# Gemma_M0_rev_D_PyCon.net
KiCad netlist of a schematic drawn in EAGLE
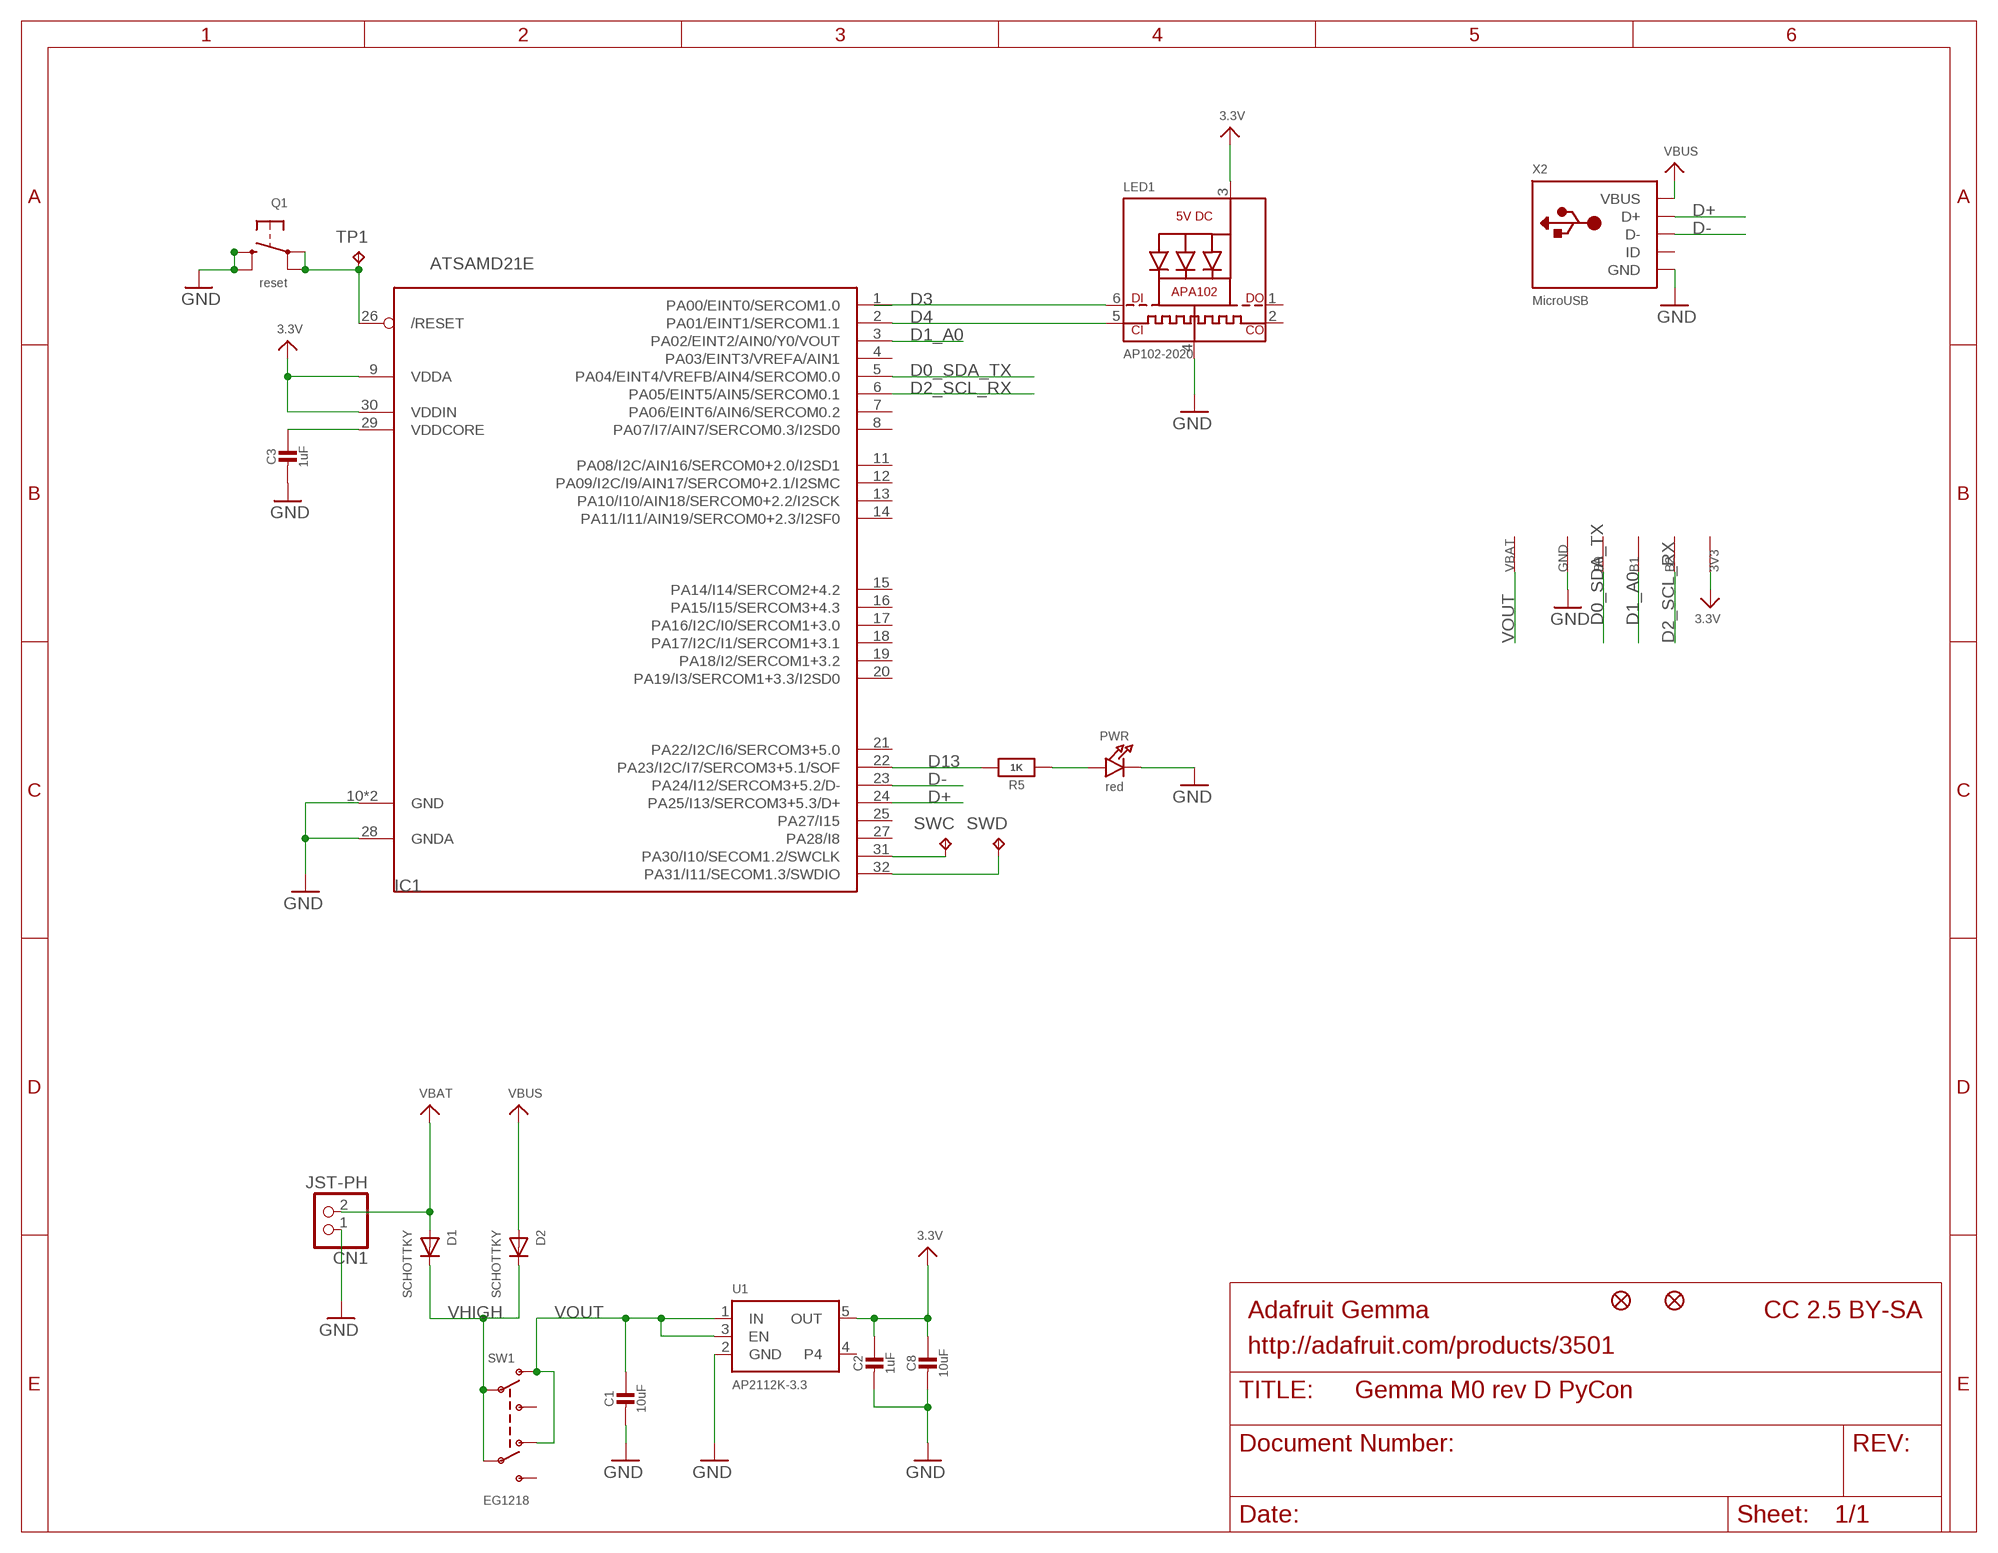
[diagram p0: schematic, sheet 1]

(export (version "E")
  (design (tool "Eeschema 10.0.6"))
  (components
    (comp (ref "3V3")
      (value "SEWTAP-ALLIGATOR")
      (footprint "eagle-import:SEWALLI")
      (libsource (lib "eagle-import") (part "SEWTAP-ALLIGATOR"))
    )
    (comp (ref "B0")
      (value "SEWTAP-ALLIGATOR")
      (footprint "eagle-import:SEWALLI")
      (libsource (lib "eagle-import") (part "SEWTAP-ALLIGATOR"))
    )
    (comp (ref "B1")
      (value "SEWTAP-ALLIGATOR")
      (footprint "eagle-import:SEWALLI")
      (libsource (lib "eagle-import") (part "SEWTAP-ALLIGATOR"))
    )
    (comp (ref "B2")
      (value "SEWTAP-ALLIGATOR")
      (footprint "eagle-import:SEWALLI")
      (libsource (lib "eagle-import") (part "SEWTAP-ALLIGATOR"))
    )
    (comp (ref "C1")
      (value "10uF")
      (footprint "eagle-import:0805-NO")
      (libsource (lib "eagle-import") (part "CAP_CERAMIC0805-NOOUTLINE"))
    )
    (comp (ref "C2")
      (value "1uF")
      (footprint "eagle-import:0603-NO")
      (libsource (lib "eagle-import") (part "CAP_CERAMIC0603_NO"))
    )
    (comp (ref "C3")
      (value "1uF")
      (footprint "eagle-import:0603-NO")
      (libsource (lib "eagle-import") (part "CAP_CERAMIC0603_NO"))
    )
    (comp (ref "C8")
      (value "10uF")
      (footprint "eagle-import:0805-NO")
      (libsource (lib "eagle-import") (part "CAP_CERAMIC0805-NOOUTLINE"))
    )
    (comp (ref "CN1")
      (value "JST-PH")
      (footprint "eagle-import:JSTPH2")
      (libsource (lib "eagle-import") (part "CON_JST_PH_2PIN"))
    )
    (comp (ref "D1")
      (value "SCHOTTKY")
      (footprint "eagle-import:SOD-123FL")
      (libsource (lib "eagle-import") (part "DIODE_SOD-123FL"))
    )
    (comp (ref "D2")
      (value "SCHOTTKY")
      (footprint "eagle-import:SOD-123FL")
      (libsource (lib "eagle-import") (part "DIODE_SOD-123FL"))
    )
    (comp (ref "GND")
      (value "SEWTAP-ALLIGATOR")
      (footprint "eagle-import:SEWALLI")
      (libsource (lib "eagle-import") (part "SEWTAP-ALLIGATOR"))
    )
    (comp (ref "IC1")
      (value "ATSAMD21E")
      (footprint "eagle-import:QFN32_5MM")
      (libsource (lib "eagle-import") (part "ATSAMD21E"))
    )
    (comp (ref "LED1")
      (value "AP102-2020")
      (footprint "eagle-import:APA102_2020")
      (libsource (lib "eagle-import") (part "APA1022020"))
    )
    (comp (ref "PWR")
      (value "red")
      (footprint "eagle-import:CHIPLED_0603_NOOUTLINE")
      (libsource (lib "eagle-import") (part "LED0603_NOOUTLINE"))
    )
    (comp (ref "Q1")
      (value "reset")
      (footprint "eagle-import:BTN_KMR2_4.6X2.8")
      (libsource (lib "eagle-import") (part "SWITCH_TACT_SMT4.6X2.8"))
    )
    (comp (ref "R5")
      (value "1K")
      (footprint "eagle-import:0603-NO")
      (libsource (lib "eagle-import") (part "RESISTOR_0603_NOOUT"))
    )
    (comp (ref "SW1")
      (value "EG1218")
      (footprint "eagle-import:EG1390")
      (libsource (lib "eagle-import") (part "SWITCH_DPDTEG1390"))
    )
    (comp (ref "SWC")
      (value "TPTP15R")
      (footprint "eagle-import:TP15R")
      (libsource (lib "eagle-import") (part "TPTP15R"))
    )
    (comp (ref "SWD")
      (value "TPTP15R")
      (footprint "eagle-import:TP15R")
      (libsource (lib "eagle-import") (part "TPTP15R"))
    )
    (comp (ref "TP1")
      (value "TPTP16R")
      (footprint "eagle-import:TP16R")
      (libsource (lib "eagle-import") (part "TPTP16R"))
    )
    (comp (ref "U$1")
      (value "FIDUCIAL_1MM")
      (footprint "eagle-import:FIDUCIAL_1MM")
      (libsource (lib "eagle-import") (part "FIDUCIAL_1MM"))
    )
    (comp (ref "U$6")
      (value "FIDUCIAL_1MM")
      (footprint "eagle-import:FIDUCIAL_1MM")
      (libsource (lib "eagle-import") (part "FIDUCIAL_1MM"))
    )
    (comp (ref "U1")
      (value "AP2112K-3.3")
      (footprint "eagle-import:SOT23-5")
      (libsource (lib "eagle-import") (part "VREG_SOT23-5"))
    )
    (comp (ref "VBAT")
      (value "SEWTAP-ALLIGATOR")
      (footprint "eagle-import:SEWALLI")
      (libsource (lib "eagle-import") (part "SEWTAP-ALLIGATOR"))
    )
    (comp (ref "X2")
      (value "MicroUSB")
      (footprint "eagle-import:4UCONN_20329_V2")
      (libsource (lib "eagle-import") (part "USB_MICRO_20329_V2"))
    )
  )
  (nets
    (net (code "1") (name "/D+") (class "Default")
      (node (ref "IC1") (pin "24") (pinfunction "PA25/I13/SERCOM3+5.3/D+_24") (pintype "bidirectional"))
      (node (ref "X2") (pin "D+") (pinfunction "D+_D+") (pintype "bidirectional"))
    )
    (net (code "2") (name "/D-") (class "Default")
      (node (ref "IC1") (pin "23") (pinfunction "PA24/I12/SERCOM3+5.2/D-_23") (pintype "bidirectional"))
      (node (ref "X2") (pin "D-") (pinfunction "D-_D-") (pintype "bidirectional"))
    )
    (net (code "3") (name "/D0_SDA_TX") (class "Default")
      (node (ref "B0") (pin "P$1") (pinfunction "SEW_P$1") (pintype "bidirectional"))
      (node (ref "IC1") (pin "5") (pinfunction "PA04/EINT4/VREFB/AIN4/SERCOM0.0_5") (pintype "bidirectional"))
    )
    (net (code "4") (name "/D1_A0") (class "Default")
      (node (ref "B1") (pin "P$1") (pinfunction "SEW_P$1") (pintype "bidirectional"))
      (node (ref "IC1") (pin "3") (pinfunction "PA02/EINT2/AIN0/Y0/VOUT_3") (pintype "bidirectional"))
    )
    (net (code "5") (name "/D2_SCL_RX") (class "Default")
      (node (ref "B2") (pin "P$1") (pinfunction "SEW_P$1") (pintype "bidirectional"))
      (node (ref "IC1") (pin "6") (pinfunction "PA05/EINT5/AIN5/SERCOM0.1_6") (pintype "bidirectional"))
    )
    (net (code "6") (name "/D3") (class "Default")
      (node (ref "IC1") (pin "1") (pinfunction "PA00/EINT0/SERCOM1.0_1") (pintype "bidirectional"))
      (node (ref "LED1") (pin "6") (pinfunction "DI_6") (pintype "input"))
    )
    (net (code "7") (name "/D4") (class "Default")
      (node (ref "IC1") (pin "2") (pinfunction "PA01/EINT1/SERCOM1.1_2") (pintype "bidirectional"))
      (node (ref "LED1") (pin "5") (pinfunction "CKI_5") (pintype "input"))
    )
    (net (code "8") (name "/D13") (class "Default")
      (node (ref "IC1") (pin "22") (pinfunction "PA23/I2C/I7/SERCOM3+5.1/SOF_22") (pintype "bidirectional"))
      (node (ref "R5") (pin "2") (pinfunction "2_2") (pintype "passive"))
    )
    (net (code "9") (name "/VHIGH") (class "Default")
      (node (ref "D1") (pin "C") (pinfunction "C_C") (pintype "passive"))
      (node (ref "D2") (pin "C") (pinfunction "C_C") (pintype "passive"))
      (node (ref "SW1") (pin "P1") (pinfunction "P1_P1") (pintype "passive"))
      (node (ref "SW1") (pin "P2") (pinfunction "P2_P2") (pintype "passive"))
    )
    (net (code "10") (name "/VOUT") (class "Default")
      (node (ref "C1") (pin "1") (pinfunction "1_1") (pintype "passive"))
      (node (ref "SW1") (pin "O1") (pinfunction "O1_O1") (pintype "passive"))
      (node (ref "SW1") (pin "O2") (pinfunction "O2_O2") (pintype "passive"))
      (node (ref "U1") (pin "1") (pinfunction "IN_1") (pintype "power_in"))
      (node (ref "U1") (pin "3") (pinfunction "EN_3") (pintype "input"))
      (node (ref "VBAT") (pin "P$1") (pinfunction "SEW_P$1") (pintype "bidirectional"))
    )
    (net (code "11") (name "3.3V") (class "Default")
      (node (ref "3V3") (pin "P$1") (pinfunction "SEW_P$1") (pintype "bidirectional"))
      (node (ref "C2") (pin "1") (pinfunction "1_1") (pintype "passive"))
      (node (ref "C8") (pin "1") (pinfunction "1_1") (pintype "passive"))
      (node (ref "IC1") (pin "30") (pinfunction "VDDIN_30") (pintype "power_in"))
      (node (ref "IC1") (pin "9") (pinfunction "VDDA_9") (pintype "power_in"))
      (node (ref "LED1") (pin "3") (pinfunction "VDD_3") (pintype "power_in"))
      (node (ref "U1") (pin "5") (pinfunction "OUT_5") (pintype "power_in"))
    )
    (net (code "12") (name "GND") (class "Default")
      (node (ref "C1") (pin "2") (pinfunction "2_2") (pintype "passive"))
      (node (ref "C2") (pin "2") (pinfunction "2_2") (pintype "passive"))
      (node (ref "C3") (pin "2") (pinfunction "2_2") (pintype "passive"))
      (node (ref "C8") (pin "2") (pinfunction "2_2") (pintype "passive"))
      (node (ref "CN1") (pin "1") (pinfunction "1_1") (pintype "passive"))
      (node (ref "GND") (pin "P$1") (pinfunction "SEW_P$1") (pintype "bidirectional"))
      (node (ref "IC1") (pin "10") (pinfunction "GND_10") (pintype "power_in"))
      (node (ref "IC1") (pin "28") (pinfunction "GNDA_28") (pintype "power_in"))
      (node (ref "IC1") (pin "33") (pinfunction "GND_33") (pintype "power_in"))
      (node (ref "LED1") (pin "4") (pinfunction "GND_4") (pintype "power_in"))
      (node (ref "PWR") (pin "C") (pinfunction "C_C") (pintype "passive"))
      (node (ref "Q1") (pin "B") (pinfunction "S_B") (pintype "passive"))
      (node (ref "Q1") (pin "B'") (pinfunction "S1_B'") (pintype "passive"))
      (node (ref "U1") (pin "2") (pinfunction "GND_2") (pintype "power_in"))
      (node (ref "X2") (pin "BASE@1") (pinfunction "GND_BASE@1") (pintype "power_in"))
      (node (ref "X2") (pin "BASE@2") (pinfunction "GND_BASE@2") (pintype "power_in"))
      (node (ref "X2") (pin "GND") (pinfunction "GND_GND") (pintype "power_in"))
      (node (ref "X2") (pin "SPRT@1") (pinfunction "GND_SPRT@1") (pintype "power_in"))
      (node (ref "X2") (pin "SPRT@2") (pinfunction "GND_SPRT@2") (pintype "power_in"))
      (node (ref "X2") (pin "SPRT@3") (pinfunction "GND_SPRT@3") (pintype "power_in"))
      (node (ref "X2") (pin "SPRT@4") (pinfunction "GND_SPRT@4") (pintype "power_in"))
    )
    (net (code "13") (name "Net-(IC1-PA30{slash}I10{slash}SECOM1.2{slash}SWCLK)") (class "Default")
      (node (ref "IC1") (pin "31") (pinfunction "PA30/I10/SECOM1.2/SWCLK_31") (pintype "bidirectional"))
      (node (ref "SWC") (pin "TP") (pinfunction "TP_TP") (pintype "input"))
    )
    (net (code "14") (name "Net-(IC1-PA31{slash}I11{slash}SECOM1.3{slash}SWDIO)") (class "Default")
      (node (ref "IC1") (pin "32") (pinfunction "PA31/I11/SECOM1.3/SWDIO_32") (pintype "bidirectional"))
      (node (ref "SWD") (pin "TP") (pinfunction "TP_TP") (pintype "input"))
    )
    (net (code "15") (name "Net-(IC1-VDDCORE)") (class "Default")
      (node (ref "C3") (pin "1") (pinfunction "1_1") (pintype "passive"))
      (node (ref "IC1") (pin "29") (pinfunction "VDDCORE_29") (pintype "power_in"))
    )
    (net (code "16") (name "Net-(IC1-{slash}RESET)") (class "Default")
      (node (ref "IC1") (pin "26") (pinfunction "/RESET_26") (pintype "bidirectional"))
      (node (ref "Q1") (pin "A") (pinfunction "P_A") (pintype "passive"))
      (node (ref "Q1") (pin "A'") (pinfunction "P1_A'") (pintype "passive"))
      (node (ref "TP1") (pin "TP") (pinfunction "TP_TP") (pintype "input"))
    )
    (net (code "17") (name "Net-(PWR-PadA)") (class "Default")
      (node (ref "PWR") (pin "A") (pinfunction "A_A") (pintype "passive"))
      (node (ref "R5") (pin "1") (pinfunction "1_1") (pintype "passive"))
    )
    (net (code "18") (name "VBAT") (class "Default")
      (node (ref "CN1") (pin "2") (pinfunction "2_2") (pintype "passive"))
      (node (ref "D1") (pin "A") (pinfunction "A_A") (pintype "passive"))
    )
    (net (code "19") (name "VBUS") (class "Default")
      (node (ref "D2") (pin "A") (pinfunction "A_A") (pintype "passive"))
      (node (ref "X2") (pin "VBUS") (pinfunction "VBUS_VBUS") (pintype "power_in"))
    )
    (net (code "20") (name "unconnected-(IC1-PA03{slash}EINT3{slash}VREFA{slash}AIN1-Pad4)") (class "Default")
      (node (ref "IC1") (pin "4") (pinfunction "PA03/EINT3/VREFA/AIN1_4") (pintype "bidirectional"))
    )
    (net (code "21") (name "unconnected-(IC1-PA06{slash}EINT6{slash}AIN6{slash}SERCOM0.2-Pad7)") (class "Default")
      (node (ref "IC1") (pin "7") (pinfunction "PA06/EINT6/AIN6/SERCOM0.2_7") (pintype "bidirectional"))
    )
    (net (code "22") (name "unconnected-(IC1-PA07{slash}I7{slash}AIN7{slash}SERCOM0.3{slash}I2SD0-Pad8)") (class "Default")
      (node (ref "IC1") (pin "8") (pinfunction "PA07/I7/AIN7/SERCOM0.3/I2SD0_8") (pintype "bidirectional"))
    )
    (net (code "23") (name "unconnected-(IC1-PA08{slash}I2C{slash}AIN16{slash}SERCOM0+2.0{slash}I2SD1-Pad11)") (class "Default")
      (node (ref "IC1") (pin "11") (pinfunction "PA08/I2C/AIN16/SERCOM0+2.0/I2SD1_11") (pintype "bidirectional"))
    )
    (net (code "24") (name "unconnected-(IC1-PA09{slash}I2C{slash}I9{slash}AIN17{slash}SERCOM0+2.1{slash}I2SMC-Pad12)") (class "Default")
      (node (ref "IC1") (pin "12") (pinfunction "PA09/I2C/I9/AIN17/SERCOM0+2.1/I2SMC_12") (pintype "bidirectional"))
    )
    (net (code "25") (name "unconnected-(IC1-PA10{slash}I10{slash}AIN18{slash}SERCOM0+2.2{slash}I2SCK-Pad13)") (class "Default")
      (node (ref "IC1") (pin "13") (pinfunction "PA10/I10/AIN18/SERCOM0+2.2/I2SCK_13") (pintype "bidirectional"))
    )
    (net (code "26") (name "unconnected-(IC1-PA11{slash}I11{slash}AIN19{slash}SERCOM0+2.3{slash}I2SF0-Pad14)") (class "Default")
      (node (ref "IC1") (pin "14") (pinfunction "PA11/I11/AIN19/SERCOM0+2.3/I2SF0_14") (pintype "bidirectional"))
    )
    (net (code "27") (name "unconnected-(IC1-PA14{slash}I14{slash}SERCOM2+4.2-Pad15)") (class "Default")
      (node (ref "IC1") (pin "15") (pinfunction "PA14/I14/SERCOM2+4.2_15") (pintype "bidirectional"))
    )
    (net (code "28") (name "unconnected-(IC1-PA15{slash}I15{slash}SERCOM3+4.3-Pad16)") (class "Default")
      (node (ref "IC1") (pin "16") (pinfunction "PA15/I15/SERCOM3+4.3_16") (pintype "bidirectional"))
    )
    (net (code "29") (name "unconnected-(IC1-PA16{slash}I2C{slash}I0{slash}SERCOM1+3.0-Pad17)") (class "Default")
      (node (ref "IC1") (pin "17") (pinfunction "PA16/I2C/I0/SERCOM1+3.0_17") (pintype "bidirectional"))
    )
    (net (code "30") (name "unconnected-(IC1-PA17{slash}I2C{slash}I1{slash}SERCOM1+3.1-Pad18)") (class "Default")
      (node (ref "IC1") (pin "18") (pinfunction "PA17/I2C/I1/SERCOM1+3.1_18") (pintype "bidirectional"))
    )
    (net (code "31") (name "unconnected-(IC1-PA18{slash}I2{slash}SERCOM1+3.2-Pad19)") (class "Default")
      (node (ref "IC1") (pin "19") (pinfunction "PA18/I2/SERCOM1+3.2_19") (pintype "bidirectional"))
    )
    (net (code "32") (name "unconnected-(IC1-PA19{slash}I3{slash}SERCOM1+3.3{slash}I2SD0-Pad20)") (class "Default")
      (node (ref "IC1") (pin "20") (pinfunction "PA19/I3/SERCOM1+3.3/I2SD0_20") (pintype "bidirectional"))
    )
    (net (code "33") (name "unconnected-(IC1-PA22{slash}I2C{slash}I6{slash}SERCOM3+5.0-Pad21)") (class "Default")
      (node (ref "IC1") (pin "21") (pinfunction "PA22/I2C/I6/SERCOM3+5.0_21") (pintype "bidirectional"))
    )
    (net (code "34") (name "unconnected-(IC1-PA27{slash}I15-Pad25)") (class "Default")
      (node (ref "IC1") (pin "25") (pinfunction "PA27/I15_25") (pintype "bidirectional"))
    )
    (net (code "35") (name "unconnected-(IC1-PA28{slash}I8-Pad27)") (class "Default")
      (node (ref "IC1") (pin "27") (pinfunction "PA28/I8_27") (pintype "bidirectional"))
    )
    (net (code "36") (name "unconnected-(LED1-CKO-Pad2)") (class "Default")
      (node (ref "LED1") (pin "2") (pinfunction "CKO_2") (pintype "output"))
    )
    (net (code "37") (name "unconnected-(LED1-DO-Pad1)") (class "Default")
      (node (ref "LED1") (pin "1") (pinfunction "DO_1") (pintype "output"))
    )
    (net (code "38") (name "unconnected-(SW1-PadS1)") (class "Default")
      (node (ref "SW1") (pin "S1") (pinfunction "S1_S1") (pintype "passive"))
    )
    (net (code "39") (name "unconnected-(SW1-PadS2)") (class "Default")
      (node (ref "SW1") (pin "S2") (pinfunction "S2_S2") (pintype "passive"))
    )
    (net (code "40") (name "unconnected-(U1-P4-Pad4)") (class "Default")
      (node (ref "U1") (pin "4") (pinfunction "P4_4") (pintype "bidirectional"))
    )
    (net (code "41") (name "unconnected-(X2-PadID)") (class "Default")
      (node (ref "X2") (pin "ID") (pinfunction "ID_ID") (pintype "bidirectional"))
    )
  )
)
